# Skematik_monitoring_tambak_ikan_lele.net
KiCad netlist of a schematic drawn in EAGLE
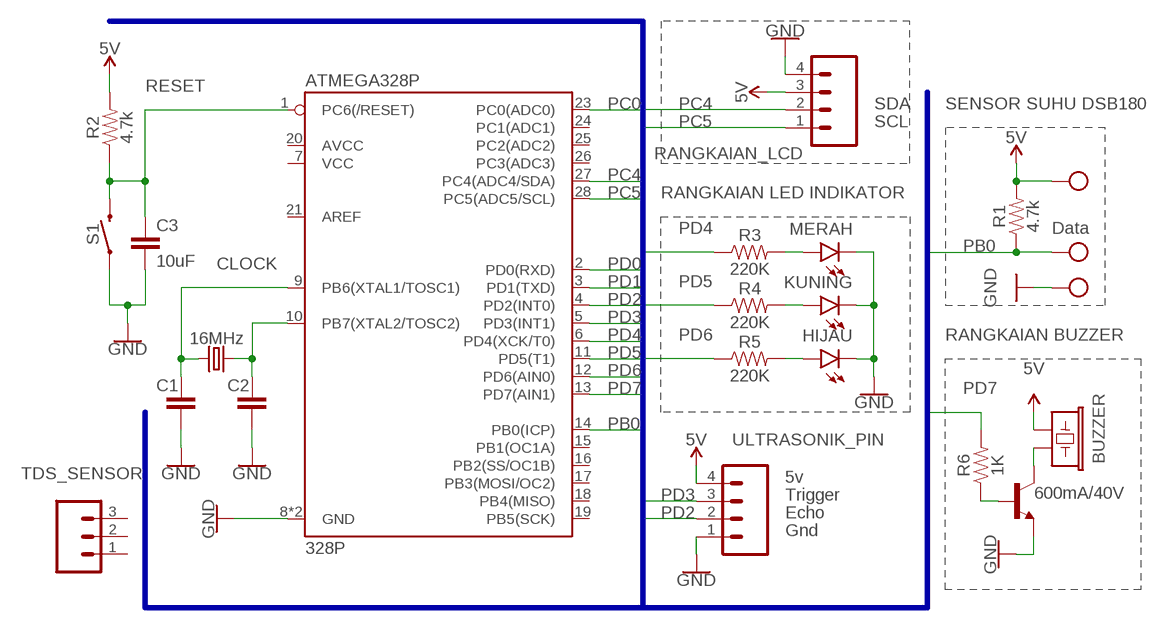
[diagram p0: schematic, sheet 1]

(export (version "E")
  (design (tool "Eeschema 10.0.6"))
  (components
    (comp (ref "ATMEGA328P")
      (value "328P")
      (footprint "eagle-import:DIP28")
      (libsource (lib "eagle-import") (part "ATMEGA328P_PDIP"))
    )
    (comp (ref "C1")
      (value "22uF")
      (footprint "eagle-import:0805")
      (libsource (lib "eagle-import") (part "22UF-0805-6.3V-20%"))
    )
    (comp (ref "C2")
      (value "22uF")
      (footprint "eagle-import:0805")
      (libsource (lib "eagle-import") (part "22UF-0805-6.3V-20%"))
    )
    (comp (ref "C3")
      (value "10uF")
      (footprint "eagle-import:0402-TIGHT")
      (libsource (lib "eagle-import") (part "10UF-0402T-6.3V-20%"))
    )
    (comp (ref "HIJAU")
      (value "LED5MM-KIT")
      (footprint "eagle-import:LED_5MM-KIT")
      (libsource (lib "eagle-import") (part "LED5MM-KIT"))
    )
    (comp (ref "KUNING")
      (value "LED5MM-KIT")
      (footprint "eagle-import:LED_5MM-KIT")
      (libsource (lib "eagle-import") (part "LED5MM-KIT"))
    )
    (comp (ref "MERAH")
      (value "LED5MM-KIT")
      (footprint "eagle-import:LED_5MM-KIT")
      (libsource (lib "eagle-import") (part "LED5MM-KIT"))
    )
    (comp (ref "Q1")
      (value "600mA/40V")
      (footprint "eagle-import:SOT23-3")
      (libsource (lib "eagle-import") (part "TRANS_NPN-MMBT2222AL"))
    )
    (comp (ref "R1")
      (value "4.7k")
      (footprint "eagle-import:0603")
      (libsource (lib "eagle-import") (part "4.7KOHM-0603-1/10W-1%"))
    )
    (comp (ref "R2")
      (value "4.7k")
      (footprint "eagle-import:0603")
      (libsource (lib "eagle-import") (part "4.7KOHM-0603-1/10W-1%"))
    )
    (comp (ref "R3")
      (value "220K")
      (footprint "eagle-import:0402-TIGHT")
      (libsource (lib "eagle-import") (part "220KOHM-0402T-1/16W-1%"))
    )
    (comp (ref "R4")
      (value "220K")
      (footprint "eagle-import:0402-TIGHT")
      (libsource (lib "eagle-import") (part "220KOHM-0402T-1/16W-1%"))
    )
    (comp (ref "R5")
      (value "220K")
      (footprint "eagle-import:0402-TIGHT")
      (libsource (lib "eagle-import") (part "220KOHM-0402T-1/16W-1%"))
    )
    (comp (ref "R6")
      (value "1K")
      (footprint "eagle-import:0402")
      (libsource (lib "eagle-import") (part "1KOHM-0402-1/16W-1%"))
    )
    (comp (ref "RANGKAIAN_LCD")
      (value "CONN_04PTH")
      (footprint "eagle-import:1X04")
      (libsource (lib "eagle-import") (part "CONN_04PTH"))
    )
    (comp (ref "S1")
      (value "Button")
      (footprint "eagle-import:TACTILE_SWITCH_PTH_6.0MM")
      (libsource (lib "eagle-import") (part "MOMENTARY-SWITCH-SPST-PTH-6.0MM"))
    )
    (comp (ref "TDS_SENSOR")
      (value "CONN_031X03_NO_SILK")
      (footprint "eagle-import:1X03_NO_SILK")
      (libsource (lib "eagle-import") (part "CONN_031X03_NO_SILK"))
    )
    (comp (ref "TRANDUZZER")
      (value "BUZZER")
      (footprint "eagle-import:BUZZER-12MM")
      (libsource (lib "eagle-import") (part "BUZZER-PTH"))
    )
    (comp (ref "ULTRASONIK_PIN")
      (value "CONN_04PTH")
      (footprint "eagle-import:1X04")
      (libsource (lib "eagle-import") (part "CONN_04PTH"))
    )
    (comp (ref "X1")
      (value "AK300/3")
      (footprint "eagle-import:AK300_3")
      (libsource (lib "eagle-import") (part "AK300/3"))
    )
    (comp (ref "Y1")
      (value "16MHz")
      (footprint "eagle-import:HC49US")
      (libsource (lib "eagle-import") (part "CRYSTAL-16MHZPTH-HC49US"))
    )
  )
  (nets
    (net (code "1") (name "/PB0") (class "Default")
      (node (ref "ATMEGA328P") (pin "14") (pinfunction "PB0(ICP)_14") (pintype "bidirectional"))
      (node (ref "R1") (pin "1") (pinfunction "1_1") (pintype "passive"))
      (node (ref "X1") (pin "2") (pinfunction "KL_2") (pintype "passive"))
    )
    (net (code "2") (name "/PC0") (class "Default")
      (node (ref "ATMEGA328P") (pin "23") (pinfunction "PC0(ADC0)_23") (pintype "bidirectional"))
    )
    (net (code "3") (name "/PC4") (class "Default")
      (node (ref "ATMEGA328P") (pin "27") (pinfunction "PC4(ADC4/SDA)_27") (pintype "bidirectional"))
      (node (ref "RANGKAIAN_LCD") (pin "2") (pinfunction "2_2") (pintype "passive"))
    )
    (net (code "4") (name "/PC5") (class "Default")
      (node (ref "ATMEGA328P") (pin "28") (pinfunction "PC5(ADC5/SCL)_28") (pintype "bidirectional"))
      (node (ref "RANGKAIAN_LCD") (pin "1") (pinfunction "1_1") (pintype "passive"))
    )
    (net (code "5") (name "/PD0") (class "Default")
      (node (ref "ATMEGA328P") (pin "2") (pinfunction "PD0(RXD)_2") (pintype "bidirectional"))
    )
    (net (code "6") (name "/PD1") (class "Default")
      (node (ref "ATMEGA328P") (pin "3") (pinfunction "PD1(TXD)_3") (pintype "bidirectional"))
    )
    (net (code "7") (name "/PD2") (class "Default")
      (node (ref "ATMEGA328P") (pin "4") (pinfunction "PD2(INT0)_4") (pintype "bidirectional"))
      (node (ref "ULTRASONIK_PIN") (pin "2") (pinfunction "2_2") (pintype "passive"))
    )
    (net (code "8") (name "/PD3") (class "Default")
      (node (ref "ATMEGA328P") (pin "5") (pinfunction "PD3(INT1)_5") (pintype "bidirectional"))
      (node (ref "ULTRASONIK_PIN") (pin "3") (pinfunction "3_3") (pintype "passive"))
    )
    (net (code "9") (name "/PD4") (class "Default")
      (node (ref "ATMEGA328P") (pin "6") (pinfunction "PD4(XCK/T0)_6") (pintype "bidirectional"))
      (node (ref "R3") (pin "1") (pinfunction "1_1") (pintype "passive"))
    )
    (net (code "10") (name "/PD5") (class "Default")
      (node (ref "ATMEGA328P") (pin "11") (pinfunction "PD5(T1)_11") (pintype "bidirectional"))
      (node (ref "R4") (pin "1") (pinfunction "1_1") (pintype "passive"))
    )
    (net (code "11") (name "/PD6") (class "Default")
      (node (ref "ATMEGA328P") (pin "12") (pinfunction "PD6(AIN0)_12") (pintype "bidirectional"))
      (node (ref "R5") (pin "1") (pinfunction "1_1") (pintype "passive"))
    )
    (net (code "12") (name "/PD7") (class "Default")
      (node (ref "ATMEGA328P") (pin "13") (pinfunction "PD7(AIN1)_13") (pintype "bidirectional"))
      (node (ref "R6") (pin "2") (pinfunction "2_2") (pintype "passive"))
    )
    (net (code "13") (name "5V") (class "Default")
      (node (ref "R1") (pin "2") (pinfunction "2_2") (pintype "passive"))
      (node (ref "R2") (pin "2") (pinfunction "2_2") (pintype "passive"))
      (node (ref "RANGKAIAN_LCD") (pin "3") (pinfunction "3_3") (pintype "passive"))
      (node (ref "TRANDUZZER") (pin "+") (pinfunction "1_+") (pintype "passive"))
      (node (ref "ULTRASONIK_PIN") (pin "4") (pinfunction "4_4") (pintype "passive"))
      (node (ref "X1") (pin "3") (pinfunction "KL_3") (pintype "passive"))
    )
    (net (code "14") (name "GND") (class "Default")
      (node (ref "ATMEGA328P") (pin "22") (pinfunction "GND_22") (pintype "bidirectional"))
      (node (ref "ATMEGA328P") (pin "8") (pinfunction "GND_8") (pintype "bidirectional"))
      (node (ref "C1") (pin "2") (pinfunction "2_2") (pintype "passive"))
      (node (ref "C2") (pin "2") (pinfunction "2_2") (pintype "passive"))
      (node (ref "C3") (pin "2") (pinfunction "2_2") (pintype "passive"))
      (node (ref "HIJAU") (pin "K") (pinfunction "C_K") (pintype "passive"))
      (node (ref "KUNING") (pin "K") (pinfunction "C_K") (pintype "passive"))
      (node (ref "MERAH") (pin "K") (pinfunction "C_K") (pintype "passive"))
      (node (ref "Q1") (pin "2") (pinfunction "E_2") (pintype "passive"))
      (node (ref "RANGKAIAN_LCD") (pin "4") (pinfunction "4_4") (pintype "passive"))
      (node (ref "S1") (pin "1") (pinfunction "1_1") (pintype "passive"))
      (node (ref "ULTRASONIK_PIN") (pin "1") (pinfunction "1_1") (pintype "passive"))
      (node (ref "X1") (pin "1") (pinfunction "KL_1") (pintype "passive"))
    )
    (net (code "15") (name "Net-(ATMEGA328P-PB6(XTAL1{slash}TOSC1))") (class "Default")
      (node (ref "ATMEGA328P") (pin "9") (pinfunction "PB6(XTAL1/TOSC1)_9") (pintype "bidirectional"))
      (node (ref "C1") (pin "1") (pinfunction "1_1") (pintype "passive"))
      (node (ref "Y1") (pin "2") (pinfunction "2_2") (pintype "passive"))
    )
    (net (code "16") (name "Net-(ATMEGA328P-PB7(XTAL2{slash}TOSC2))") (class "Default")
      (node (ref "ATMEGA328P") (pin "10") (pinfunction "PB7(XTAL2/TOSC2)_10") (pintype "bidirectional"))
      (node (ref "C2") (pin "1") (pinfunction "1_1") (pintype "passive"))
      (node (ref "Y1") (pin "1") (pinfunction "1_1") (pintype "passive"))
    )
    (net (code "17") (name "Net-(ATMEGA328P-PC6({slash}RESET))") (class "Default")
      (node (ref "ATMEGA328P") (pin "1") (pinfunction "PC6(/RESET)_1") (pintype "bidirectional"))
      (node (ref "C3") (pin "1") (pinfunction "1_1") (pintype "passive"))
      (node (ref "R2") (pin "1") (pinfunction "1_1") (pintype "passive"))
      (node (ref "S1") (pin "3") (pinfunction "2_3") (pintype "passive"))
    )
    (net (code "18") (name "Net-(HIJAU-PadA)") (class "Default")
      (node (ref "HIJAU") (pin "A") (pinfunction "A_A") (pintype "passive"))
      (node (ref "R5") (pin "2") (pinfunction "2_2") (pintype "passive"))
    )
    (net (code "19") (name "Net-(KUNING-PadA)") (class "Default")
      (node (ref "KUNING") (pin "A") (pinfunction "A_A") (pintype "passive"))
      (node (ref "R4") (pin "2") (pinfunction "2_2") (pintype "passive"))
    )
    (net (code "20") (name "Net-(MERAH-PadA)") (class "Default")
      (node (ref "MERAH") (pin "A") (pinfunction "A_A") (pintype "passive"))
      (node (ref "R3") (pin "2") (pinfunction "2_2") (pintype "passive"))
    )
    (net (code "21") (name "Net-(Q1-B)") (class "Default")
      (node (ref "Q1") (pin "1") (pinfunction "B_1") (pintype "passive"))
      (node (ref "R6") (pin "1") (pinfunction "1_1") (pintype "passive"))
    )
    (net (code "22") (name "Net-(Q1-C)") (class "Default")
      (node (ref "Q1") (pin "3") (pinfunction "C_3") (pintype "passive"))
      (node (ref "TRANDUZZER") (pin "-") (pinfunction "2_-") (pintype "passive"))
    )
    (net (code "23") (name "unconnected-(ATMEGA328P-AREF-Pad21)") (class "Default")
      (node (ref "ATMEGA328P") (pin "21") (pinfunction "AREF_21") (pintype "bidirectional"))
    )
    (net (code "24") (name "unconnected-(ATMEGA328P-AVCC-Pad20)") (class "Default")
      (node (ref "ATMEGA328P") (pin "20") (pinfunction "AVCC_20") (pintype "bidirectional"))
    )
    (net (code "25") (name "unconnected-(ATMEGA328P-PB1(OC1A)-Pad15)") (class "Default")
      (node (ref "ATMEGA328P") (pin "15") (pinfunction "PB1(OC1A)_15") (pintype "bidirectional"))
    )
    (net (code "26") (name "unconnected-(ATMEGA328P-PB2(SS{slash}OC1B)-Pad16)") (class "Default")
      (node (ref "ATMEGA328P") (pin "16") (pinfunction "PB2(SS/OC1B)_16") (pintype "bidirectional"))
    )
    (net (code "27") (name "unconnected-(ATMEGA328P-PB3(MOSI{slash}OC2)-Pad17)") (class "Default")
      (node (ref "ATMEGA328P") (pin "17") (pinfunction "PB3(MOSI/OC2)_17") (pintype "bidirectional"))
    )
    (net (code "28") (name "unconnected-(ATMEGA328P-PB4(MISO)-Pad18)") (class "Default")
      (node (ref "ATMEGA328P") (pin "18") (pinfunction "PB4(MISO)_18") (pintype "bidirectional"))
    )
    (net (code "29") (name "unconnected-(ATMEGA328P-PB5(SCK)-Pad19)") (class "Default")
      (node (ref "ATMEGA328P") (pin "19") (pinfunction "PB5(SCK)_19") (pintype "bidirectional"))
    )
    (net (code "30") (name "unconnected-(ATMEGA328P-PC1(ADC1)-Pad24)") (class "Default")
      (node (ref "ATMEGA328P") (pin "24") (pinfunction "PC1(ADC1)_24") (pintype "bidirectional"))
    )
    (net (code "31") (name "unconnected-(ATMEGA328P-PC2(ADC2)-Pad25)") (class "Default")
      (node (ref "ATMEGA328P") (pin "25") (pinfunction "PC2(ADC2)_25") (pintype "bidirectional"))
    )
    (net (code "32") (name "unconnected-(ATMEGA328P-PC3(ADC3)-Pad26)") (class "Default")
      (node (ref "ATMEGA328P") (pin "26") (pinfunction "PC3(ADC3)_26") (pintype "bidirectional"))
    )
    (net (code "33") (name "unconnected-(ATMEGA328P-VCC-Pad7)") (class "Default")
      (node (ref "ATMEGA328P") (pin "7") (pinfunction "VCC_7") (pintype "bidirectional"))
    )
    (net (code "34") (name "unconnected-(TDS_SENSOR-Pad1)") (class "Default")
      (node (ref "TDS_SENSOR") (pin "1") (pinfunction "1_1") (pintype "passive"))
    )
    (net (code "35") (name "unconnected-(TDS_SENSOR-Pad2)") (class "Default")
      (node (ref "TDS_SENSOR") (pin "2") (pinfunction "2_2") (pintype "passive"))
    )
    (net (code "36") (name "unconnected-(TDS_SENSOR-Pad3)") (class "Default")
      (node (ref "TDS_SENSOR") (pin "3") (pinfunction "3_3") (pintype "passive"))
    )
  )
)
